# 1_Wearable_Air_Quality_Pendant.net
KiCad netlist of a schematic drawn in Altium Designer
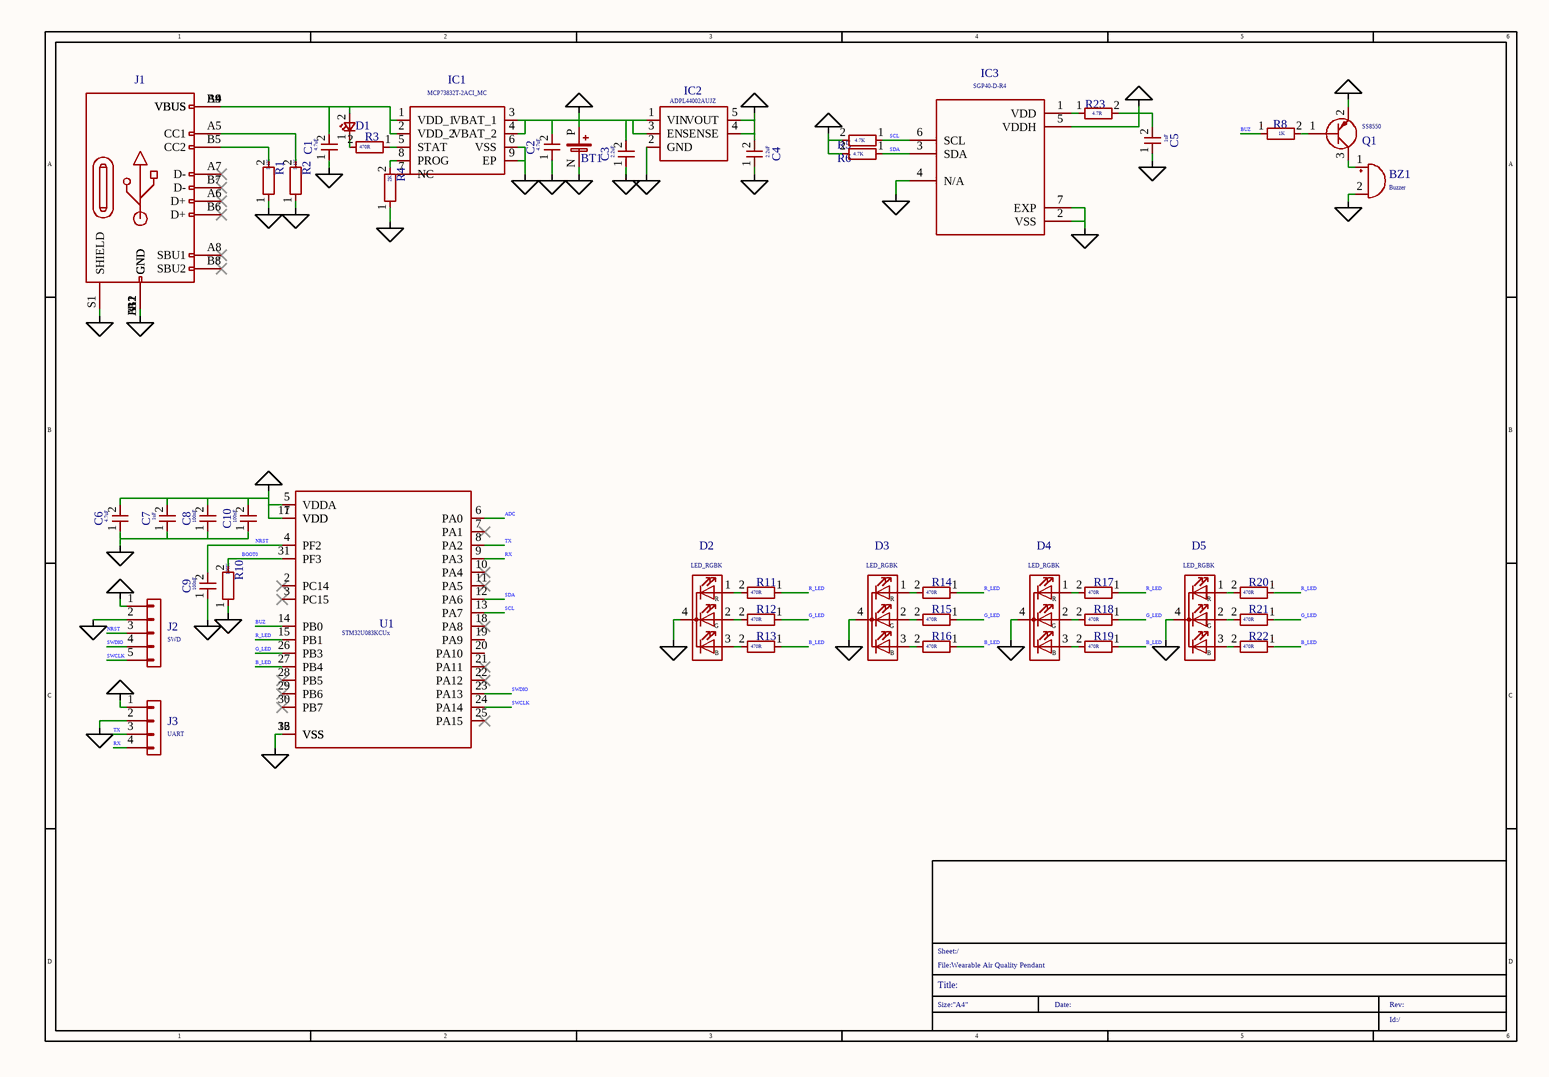
[diagram p0: 1_Wearable Air Quality Pendant.schdoc]

(export (version "E")
  (design (tool "Eeschema 10.0.6"))
  (components
    (comp (ref "BT1")
      (value "Device_Battery_Cell")
      (footprint "1060:BAT_1060")
      (libsource (lib "altium-import") (part "root_0_Device_Battery_Cell_"))
    )
    (comp (ref "BZ1")
      (value "Device_Buzzer")
      (footprint "PKMCS0909E4000_R1:PKMCS0909E4000-R1_MUR")
      (fields (field (name "ALTIUM_VALUE") "Buzzer"))
      (libsource (lib "altium-import") (part "root_0_Device_Buzzer_"))
    )
    (comp (ref "C1")
      (value "Device_C_Small")
      (footprint "Capacitor_SMD:C_0603_1608Metric")
      (fields (field (name "ALTIUM_VALUE") "4.7uF"))
      (libsource (lib "altium-import") (part "root_2_Device_C_Small_"))
    )
    (comp (ref "C2")
      (value "Device_C_Small")
      (footprint "Capacitor_SMD:C_0603_1608Metric")
      (fields (field (name "ALTIUM_VALUE") "4.7uF"))
      (libsource (lib "altium-import") (part "root_2_Device_C_Small_"))
    )
    (comp (ref "C3")
      (value "Device_C_Small")
      (footprint "Capacitor_SMD:C_0603_1608Metric")
      (fields (field (name "ALTIUM_VALUE") "2.2uF"))
      (libsource (lib "altium-import") (part "root_2_Device_C_Small_"))
    )
    (comp (ref "C4")
      (value "Device_C_Small")
      (footprint "Capacitor_SMD:C_0603_1608Metric")
      (fields (field (name "ALTIUM_VALUE") "2.2uF"))
      (libsource (lib "altium-import") (part "root_2_mirrored_Device_C_Small_"))
    )
    (comp (ref "C5")
      (value "Device_C_Small")
      (footprint "Capacitor_SMD:C_0603_1608Metric")
      (fields (field (name "ALTIUM_VALUE") "1uF"))
      (libsource (lib "altium-import") (part "root_2_mirrored_Device_C_Small_"))
    )
    (comp (ref "C6")
      (value "Device_C_Small")
      (footprint "Capacitor_SMD:C_0603_1608Metric")
      (fields (field (name "ALTIUM_VALUE") "4.7uF"))
      (libsource (lib "altium-import") (part "root_2_Device_C_Small_"))
    )
    (comp (ref "C7")
      (value "Device_C_Small")
      (footprint "Capacitor_SMD:C_0603_1608Metric")
      (fields (field (name "ALTIUM_VALUE") "1uF"))
      (libsource (lib "altium-import") (part "root_2_Device_C_Small_"))
    )
    (comp (ref "C8")
      (value "Device_C_Small")
      (footprint "Capacitor_SMD:C_0603_1608Metric")
      (fields (field (name "ALTIUM_VALUE") "100nF"))
      (libsource (lib "altium-import") (part "root_2_Device_C_Small_"))
    )
    (comp (ref "C9")
      (value "Device_C_Small")
      (footprint "Capacitor_SMD:C_0603_1608Metric")
      (fields (field (name "ALTIUM_VALUE") "100nF"))
      (libsource (lib "altium-import") (part "root_2_Device_C_Small_"))
    )
    (comp (ref "C10")
      (value "Device_C_Small")
      (footprint "Capacitor_SMD:C_0603_1608Metric")
      (fields (field (name "ALTIUM_VALUE") "100nF"))
      (libsource (lib "altium-import") (part "root_2_Device_C_Small_"))
    )
    (comp (ref "D1")
      (value "Device_LED_Small")
      (footprint "LED_SMD:LED_0603_1608Metric")
      (libsource (lib "altium-import") (part "root_1_Device_LED_Small_"))
    )
    (comp (ref "D2")
      (value "Device_LED_RGBK")
      (footprint "EAST1616RGBA1:EAST1616RGBA1")
      (fields (field (name "ALTIUM_VALUE") "LED_RGBK"))
      (libsource (lib "altium-import") (part "root_0_Device_LED_RGBK_"))
    )
    (comp (ref "D3")
      (value "Device_LED_RGBK")
      (footprint "EAST1616RGBA1:EAST1616RGBA1")
      (fields (field (name "ALTIUM_VALUE") "LED_RGBK"))
      (libsource (lib "altium-import") (part "root_0_Device_LED_RGBK_"))
    )
    (comp (ref "D4")
      (value "Device_LED_RGBK")
      (footprint "EAST1616RGBA1:EAST1616RGBA1")
      (fields (field (name "ALTIUM_VALUE") "LED_RGBK"))
      (libsource (lib "altium-import") (part "root_0_Device_LED_RGBK_"))
    )
    (comp (ref "D5")
      (value "Device_LED_RGBK")
      (footprint "EAST1616RGBA1:EAST1616RGBA1")
      (fields (field (name "ALTIUM_VALUE") "LED_RGBK"))
      (libsource (lib "altium-import") (part "root_0_Device_LED_RGBK_"))
    )
    (comp (ref "IC1")
      (value "MCP73832T-2ACI_MC_MCP73832T-2ACI_MC")
      (footprint "MCP73832T-2ACI_MC:SON50P300X200X100-9N-D")
      (fields
        (field (name "MOUSER PART NUMBER") "579-MCP73832T-2ACIMC")
        (field (name "MANUFACTURER_PART_NUMBER") "MCP73832T-2ACI/MC")
        (field (name "ALTIUM_VALUE") "MCP73832T-2ACI_MC")
      )
      (libsource (lib "altium-import") (part "root_0_MCP73832T-2ACI_MC_MCP73832T-2ACI_MC_"))
    )
    (comp (ref "IC2")
      (value "ADPL44002AUJZ-3_3-R7_ADPL44002AUJZ-3.3-R7")
      (footprint "ADPL44002AUJZ-3.3-R7:SOT95P280X100-5N")
      (fields
        (field (name "MANUFACTURER_PART_NUMBER") "ADPL44002AUJZ2.5-R7")
        (field (name "ALTIUM_VALUE") "ADPL44002AUJZ")
      )
      (libsource (lib "altium-import") (part "root_0_ADPL44002AUJZ-3_3-R7_ADPL44002AUJZ-3.3-R7_"))
    )
    (comp (ref "IC3")
      (value "SGP40-D-R4_SGP40-D-R4")
      (footprint "SGP40_D_R4:XCDR_SGP40-D-R4")
      (fields (field (name "MANUFACTURER") "Sensirion AG") (field (name "ALTIUM_VALUE") "SGP40-D-R4"))
      (libsource (lib "altium-import") (part "root_0_SGP40-D-R4_SGP40-D-R4_"))
    )
    (comp (ref "J1")
      (value "Connector_USB_C_Receptacle_USB2.0_16P")
      (footprint "Connector_USB:USB_C_Receptacle_Palconn_UTC16-G")
      (libsource (lib "altium-import") (part "root_0_Connector_USB_C_Receptacle_USB2.0_16P_"))
    )
    (comp (ref "J2")
      (value "Connector_Generic_Conn_01x05")
      (footprint "Connector_PinHeader_1.27mm:PinHeader_1x06_P1.27mm_Vertical")
      (fields (field (name "ALTIUM_VALUE") "SWD"))
      (libsource (lib "altium-import") (part "root_0_Connector_Generic_Conn_01x05_"))
    )
    (comp (ref "J3")
      (value "Connector_Generic_Conn_01x04")
      (footprint "Connector_PinHeader_1.27mm:PinHeader_1x04_P1.27mm_Vertical")
      (fields (field (name "ALTIUM_VALUE") "UART"))
      (libsource (lib "altium-import") (part "root_0_Connector_Generic_Conn_01x04_"))
    )
    (comp (ref "Q1")
      (value "Transistor_BJT_SS8550")
      (footprint "Package_TO_SOT_SMD:SOT-23")
      (fields (field (name "ALTIUM_VALUE") "SS8550"))
      (libsource (lib "altium-import") (part "root_2_mirrored_Transistor_BJT_SS8550_"))
    )
    (comp (ref "R1")
      (value "Device_R")
      (footprint "Resistor_SMD:R_0603_1608Metric")
      (fields (field (name "ALTIUM_VALUE") "5.1K"))
      (libsource (lib "altium-import") (part "root_2_Device_R_"))
    )
    (comp (ref "R2")
      (value "Device_R")
      (footprint "Resistor_SMD:R_0603_1608Metric")
      (fields (field (name "ALTIUM_VALUE") "5.1K"))
      (libsource (lib "altium-import") (part "root_2_Device_R_"))
    )
    (comp (ref "R3")
      (value "Device_R")
      (footprint "Resistor_SMD:R_0603_1608Metric")
      (fields (field (name "ALTIUM_VALUE") "470R"))
      (libsource (lib "altium-import") (part "root_3_Device_R_"))
    )
    (comp (ref "R4")
      (value "Device_R")
      (footprint "Resistor_SMD:R_0603_1608Metric")
      (fields (field (name "ALTIUM_VALUE") "2K"))
      (libsource (lib "altium-import") (part "root_2_Device_R_"))
    )
    (comp (ref "R5")
      (value "Device_R")
      (footprint "Resistor_SMD:R_0603_1608Metric")
      (fields (field (name "ALTIUM_VALUE") "4.7K"))
      (libsource (lib "altium-import") (part "root_3_Device_R_"))
    )
    (comp (ref "R6")
      (value "Device_R")
      (footprint "Resistor_SMD:R_0603_1608Metric")
      (fields (field (name "ALTIUM_VALUE") "4.7K"))
      (libsource (lib "altium-import") (part "root_1_mirrored_Device_R_"))
    )
    (comp (ref "R8")
      (value "Device_R")
      (footprint "Resistor_SMD:R_0603_1608Metric")
      (fields (field (name "ALTIUM_VALUE") "1K"))
      (libsource (lib "altium-import") (part "root_3_mirrored_Device_R_"))
    )
    (comp (ref "R10")
      (value "Device_R")
      (footprint "Resistor_SMD:R_0603_1608Metric")
      (fields (field (name "ALTIUM_VALUE") "100K"))
      (libsource (lib "altium-import") (part "root_2_Device_R_"))
    )
    (comp (ref "R11")
      (value "Device_R")
      (footprint "Resistor_SMD:R_0603_1608Metric")
      (fields (field (name "ALTIUM_VALUE") "470R"))
      (libsource (lib "altium-import") (part "root_3_Device_R_"))
    )
    (comp (ref "R12")
      (value "Device_R")
      (footprint "Resistor_SMD:R_0603_1608Metric")
      (fields (field (name "ALTIUM_VALUE") "470R"))
      (libsource (lib "altium-import") (part "root_3_Device_R_"))
    )
    (comp (ref "R13")
      (value "Device_R")
      (footprint "Resistor_SMD:R_0603_1608Metric")
      (fields (field (name "ALTIUM_VALUE") "470R"))
      (libsource (lib "altium-import") (part "root_3_Device_R_"))
    )
    (comp (ref "R14")
      (value "Device_R")
      (footprint "Resistor_SMD:R_0603_1608Metric")
      (fields (field (name "ALTIUM_VALUE") "470R"))
      (libsource (lib "altium-import") (part "root_3_Device_R_"))
    )
    (comp (ref "R15")
      (value "Device_R")
      (footprint "Resistor_SMD:R_0603_1608Metric")
      (fields (field (name "ALTIUM_VALUE") "470R"))
      (libsource (lib "altium-import") (part "root_3_Device_R_"))
    )
    (comp (ref "R16")
      (value "Device_R")
      (footprint "Resistor_SMD:R_0603_1608Metric")
      (fields (field (name "ALTIUM_VALUE") "470R"))
      (libsource (lib "altium-import") (part "root_3_Device_R_"))
    )
    (comp (ref "R17")
      (value "Device_R")
      (footprint "Resistor_SMD:R_0603_1608Metric")
      (fields (field (name "ALTIUM_VALUE") "470R"))
      (libsource (lib "altium-import") (part "root_3_Device_R_"))
    )
    (comp (ref "R18")
      (value "Device_R")
      (footprint "Resistor_SMD:R_0603_1608Metric")
      (fields (field (name "ALTIUM_VALUE") "470R"))
      (libsource (lib "altium-import") (part "root_3_Device_R_"))
    )
    (comp (ref "R19")
      (value "Device_R")
      (footprint "Resistor_SMD:R_0603_1608Metric")
      (fields (field (name "ALTIUM_VALUE") "470R"))
      (libsource (lib "altium-import") (part "root_3_Device_R_"))
    )
    (comp (ref "R20")
      (value "Device_R")
      (footprint "Resistor_SMD:R_0603_1608Metric")
      (fields (field (name "ALTIUM_VALUE") "470R"))
      (libsource (lib "altium-import") (part "root_3_Device_R_"))
    )
    (comp (ref "R21")
      (value "Device_R")
      (footprint "Resistor_SMD:R_0603_1608Metric")
      (fields (field (name "ALTIUM_VALUE") "470R"))
      (libsource (lib "altium-import") (part "root_3_Device_R_"))
    )
    (comp (ref "R22")
      (value "Device_R")
      (footprint "Resistor_SMD:R_0603_1608Metric")
      (fields (field (name "ALTIUM_VALUE") "470R"))
      (libsource (lib "altium-import") (part "root_3_Device_R_"))
    )
    (comp (ref "R23")
      (value "Device_R")
      (footprint "Resistor_SMD:R_0805_2012Metric")
      (fields (field (name "ALTIUM_VALUE") "4.7R"))
      (libsource (lib "altium-import") (part "root_3_mirrored_Device_R_"))
    )
    (comp (ref "U1")
      (value "MCU_ST_STM32U0_STM32U083KCUx")
      (footprint "Package_DFN_QFN:QFN-32-1EP_5x5mm_P0.5mm_EP3.45x3.45mm")
      (fields (field (name "ALTIUM_VALUE") "STM32U083KCUx"))
      (libsource (lib "altium-import") (part "root_0_MCU_ST_STM32U0_STM32U083KCUx_"))
    )
  )
  (nets
    (net (code "1") (name "/ADC") (class "Default")
      (node (ref "U1") (pin "6") (pinfunction "PA0_6") (pintype "passive"))
    )
    (net (code "2") (name "/BOOT0") (class "Default")
      (node (ref "R10") (pin "2") (pintype "passive"))
      (node (ref "U1") (pin "31") (pinfunction "PF3_31") (pintype "passive"))
    )
    (net (code "3") (name "/BUZ") (class "Default")
      (node (ref "R8") (pin "1") (pintype "passive"))
      (node (ref "U1") (pin "14") (pinfunction "PB0_14") (pintype "passive"))
    )
    (net (code "4") (name "/B_LED") (class "Default")
      (node (ref "R13") (pin "1") (pintype "passive"))
      (node (ref "R16") (pin "1") (pintype "passive"))
      (node (ref "R19") (pin "1") (pintype "passive"))
      (node (ref "R22") (pin "1") (pintype "passive"))
      (node (ref "U1") (pin "27") (pinfunction "PB4_27") (pintype "passive"))
    )
    (net (code "5") (name "/G_LED") (class "Default")
      (node (ref "R12") (pin "1") (pintype "passive"))
      (node (ref "R15") (pin "1") (pintype "passive"))
      (node (ref "R18") (pin "1") (pintype "passive"))
      (node (ref "R21") (pin "1") (pintype "passive"))
      (node (ref "U1") (pin "26") (pinfunction "PB3_26") (pintype "passive"))
    )
    (net (code "6") (name "/NRST") (class "Default")
      (node (ref "C9") (pin "2") (pintype "passive"))
      (node (ref "J2") (pin "3") (pinfunction "Pin_3_3") (pintype "passive"))
      (node (ref "U1") (pin "4") (pinfunction "PF2_4") (pintype "passive"))
    )
    (net (code "7") (name "/RX") (class "Default")
      (node (ref "J3") (pin "4") (pinfunction "Pin_4_4") (pintype "passive"))
      (node (ref "U1") (pin "9") (pinfunction "PA3_9") (pintype "passive"))
    )
    (net (code "8") (name "/R_LED") (class "Default")
      (node (ref "R11") (pin "1") (pintype "passive"))
      (node (ref "R14") (pin "1") (pintype "passive"))
      (node (ref "R17") (pin "1") (pintype "passive"))
      (node (ref "R20") (pin "1") (pintype "passive"))
      (node (ref "U1") (pin "15") (pinfunction "PB1_15") (pintype "passive"))
    )
    (net (code "9") (name "/SCL") (class "Default")
      (node (ref "IC3") (pin "6") (pinfunction "SCL_6") (pintype "passive"))
      (node (ref "R5") (pin "1") (pintype "passive"))
      (node (ref "U1") (pin "13") (pinfunction "PA7_13") (pintype "passive"))
    )
    (net (code "10") (name "/SDA") (class "Default")
      (node (ref "IC3") (pin "3") (pinfunction "SDA_3") (pintype "passive"))
      (node (ref "R6") (pin "1") (pintype "passive"))
      (node (ref "U1") (pin "12") (pinfunction "PA6_12") (pintype "passive"))
    )
    (net (code "11") (name "/SWCLK") (class "Default")
      (node (ref "J2") (pin "5") (pinfunction "Pin_5_5") (pintype "passive"))
      (node (ref "U1") (pin "24") (pinfunction "PA14_24") (pintype "passive"))
    )
    (net (code "12") (name "/SWDIO") (class "Default")
      (node (ref "J2") (pin "4") (pinfunction "Pin_4_4") (pintype "passive"))
      (node (ref "U1") (pin "23") (pinfunction "PA13_23") (pintype "passive"))
    )
    (net (code "13") (name "/TX") (class "Default")
      (node (ref "J3") (pin "3") (pinfunction "Pin_3_3") (pintype "passive"))
      (node (ref "U1") (pin "8") (pinfunction "PA2_8") (pintype "passive"))
    )
    (net (code "14") (name "Net-(BZ1-+)") (class "Default")
      (node (ref "BZ1") (pin "1") (pinfunction "+_1") (pintype "passive"))
      (node (ref "Q1") (pin "3") (pinfunction "C_3") (pintype "passive"))
    )
    (net (code "15") (name "Net-(D1-A)") (class "Default")
      (node (ref "C1") (pin "2") (pintype "passive"))
      (node (ref "D1") (pin "2") (pinfunction "A_2") (pintype "passive"))
      (node (ref "IC1") (pin "1") (pinfunction "VDD_1_1") (pintype "passive"))
      (node (ref "IC1") (pin "2") (pinfunction "VDD_2_2") (pintype "passive"))
      (node (ref "J1") (pin "A4") (pinfunction "VBUS_A4") (pintype "passive"))
      (node (ref "J1") (pin "A9") (pinfunction "VBUS_A9") (pintype "passive"))
      (node (ref "J1") (pin "B4") (pinfunction "VBUS_B4") (pintype "passive"))
      (node (ref "J1") (pin "B9") (pinfunction "VBUS_B9") (pintype "passive"))
    )
    (net (code "16") (name "Net-(D1-K)") (class "Default")
      (node (ref "D1") (pin "1") (pinfunction "K_1") (pintype "passive"))
      (node (ref "R3") (pin "2") (pintype "passive"))
    )
    (net (code "17") (name "Net-(D2-BA)") (class "Default")
      (node (ref "D2") (pin "3") (pinfunction "BA_3") (pintype "passive"))
      (node (ref "R13") (pin "2") (pintype "passive"))
    )
    (net (code "18") (name "Net-(D2-GA)") (class "Default")
      (node (ref "D2") (pin "2") (pinfunction "GA_2") (pintype "passive"))
      (node (ref "R12") (pin "2") (pintype "passive"))
    )
    (net (code "19") (name "Net-(D2-RA)") (class "Default")
      (node (ref "D2") (pin "1") (pinfunction "RA_1") (pintype "passive"))
      (node (ref "R11") (pin "2") (pintype "passive"))
    )
    (net (code "20") (name "Net-(D3-BA)") (class "Default")
      (node (ref "D3") (pin "3") (pinfunction "BA_3") (pintype "passive"))
      (node (ref "R16") (pin "2") (pintype "passive"))
    )
    (net (code "21") (name "Net-(D3-GA)") (class "Default")
      (node (ref "D3") (pin "2") (pinfunction "GA_2") (pintype "passive"))
      (node (ref "R15") (pin "2") (pintype "passive"))
    )
    (net (code "22") (name "Net-(D3-RA)") (class "Default")
      (node (ref "D3") (pin "1") (pinfunction "RA_1") (pintype "passive"))
      (node (ref "R14") (pin "2") (pintype "passive"))
    )
    (net (code "23") (name "Net-(D4-BA)") (class "Default")
      (node (ref "D4") (pin "3") (pinfunction "BA_3") (pintype "passive"))
      (node (ref "R19") (pin "2") (pintype "passive"))
    )
    (net (code "24") (name "Net-(D4-GA)") (class "Default")
      (node (ref "D4") (pin "2") (pinfunction "GA_2") (pintype "passive"))
      (node (ref "R18") (pin "2") (pintype "passive"))
    )
    (net (code "25") (name "Net-(D4-RA)") (class "Default")
      (node (ref "D4") (pin "1") (pinfunction "RA_1") (pintype "passive"))
      (node (ref "R17") (pin "2") (pintype "passive"))
    )
    (net (code "26") (name "Net-(D5-BA)") (class "Default")
      (node (ref "D5") (pin "3") (pinfunction "BA_3") (pintype "passive"))
      (node (ref "R22") (pin "2") (pintype "passive"))
    )
    (net (code "27") (name "Net-(D5-GA)") (class "Default")
      (node (ref "D5") (pin "2") (pinfunction "GA_2") (pintype "passive"))
      (node (ref "R21") (pin "2") (pintype "passive"))
    )
    (net (code "28") (name "Net-(D5-RA)") (class "Default")
      (node (ref "D5") (pin "1") (pinfunction "RA_1") (pintype "passive"))
      (node (ref "R20") (pin "2") (pintype "passive"))
    )
    (net (code "29") (name "Net-(IC1-PROG)") (class "Default")
      (node (ref "IC1") (pin "8") (pinfunction "PROG_8") (pintype "passive"))
      (node (ref "R4") (pin "2") (pintype "passive"))
    )
    (net (code "30") (name "Net-(IC1-STAT)") (class "Default")
      (node (ref "IC1") (pin "5") (pinfunction "STAT_5") (pintype "passive"))
      (node (ref "R3") (pin "1") (pintype "passive"))
    )
    (net (code "31") (name "Net-(IC3-VDD)") (class "Default")
      (node (ref "IC3") (pin "1") (pinfunction "VDD_1") (pintype "passive"))
      (node (ref "R23") (pin "1") (pintype "passive"))
    )
    (net (code "32") (name "Net-(J1-CC1)") (class "Default")
      (node (ref "J1") (pin "A5") (pinfunction "CC1_A5") (pintype "passive"))
      (node (ref "R2") (pin "2") (pintype "passive"))
    )
    (net (code "33") (name "Net-(J1-CC2)") (class "Default")
      (node (ref "J1") (pin "B5") (pinfunction "CC2_B5") (pintype "passive"))
      (node (ref "R1") (pin "2") (pintype "passive"))
    )
    (net (code "34") (name "Net-(Q1-B)") (class "Default")
      (node (ref "Q1") (pin "1") (pinfunction "B_1") (pintype "passive"))
      (node (ref "R8") (pin "2") (pintype "passive"))
    )
    (net (code "35") (name "POWER_+3.3V") (class "Default")
      (node (ref "C10") (pin "2") (pintype "passive"))
      (node (ref "C4") (pin "2") (pintype "passive"))
      (node (ref "C5") (pin "2") (pintype "passive"))
      (node (ref "C6") (pin "2") (pintype "passive"))
      (node (ref "C7") (pin "2") (pintype "passive"))
      (node (ref "C8") (pin "2") (pintype "passive"))
      (node (ref "IC2") (pin "4") (pinfunction "SENSE_4") (pintype "passive"))
      (node (ref "IC2") (pin "5") (pinfunction "VOUT_5") (pintype "passive"))
      (node (ref "IC3") (pin "5") (pinfunction "VDDH_5") (pintype "passive"))
      (node (ref "J2") (pin "1") (pinfunction "Pin_1_1") (pintype "passive"))
      (node (ref "J3") (pin "1") (pinfunction "Pin_1_1") (pintype "passive"))
      (node (ref "Q1") (pin "2") (pinfunction "E_2") (pintype "passive"))
      (node (ref "R23") (pin "2") (pintype "passive"))
      (node (ref "R5") (pin "2") (pintype "passive"))
      (node (ref "R6") (pin "2") (pintype "passive"))
      (node (ref "U1") (pin "1") (pinfunction "VDD_1") (pintype "passive"))
      (node (ref "U1") (pin "17") (pinfunction "VDD_17") (pintype "passive"))
      (node (ref "U1") (pin "5") (pinfunction "VDDA_5") (pintype "passive"))
    )
    (net (code "36") (name "POWER_+BATT") (class "Default")
      (node (ref "BT1") (pin "P") (pinfunction "+_P") (pintype "passive"))
      (node (ref "C2") (pin "2") (pintype "passive"))
      (node (ref "C3") (pin "2") (pintype "passive"))
      (node (ref "IC1") (pin "3") (pinfunction "VBAT_1_3") (pintype "passive"))
      (node (ref "IC1") (pin "4") (pinfunction "VBAT_2_4") (pintype "passive"))
      (node (ref "IC2") (pin "1") (pinfunction "VIN_1") (pintype "passive"))
      (node (ref "IC2") (pin "3") (pinfunction "EN_3") (pintype "passive"))
    )
    (net (code "37") (name "POWER_GND") (class "Default")
      (node (ref "BT1") (pin "N") (pinfunction "-_N") (pintype "passive"))
      (node (ref "BZ1") (pin "2") (pinfunction "-_2") (pintype "passive"))
      (node (ref "C1") (pin "1") (pintype "passive"))
      (node (ref "C10") (pin "1") (pintype "passive"))
      (node (ref "C2") (pin "1") (pintype "passive"))
      (node (ref "C3") (pin "1") (pintype "passive"))
      (node (ref "C4") (pin "1") (pintype "passive"))
      (node (ref "C5") (pin "1") (pintype "passive"))
      (node (ref "C6") (pin "1") (pintype "passive"))
      (node (ref "C7") (pin "1") (pintype "passive"))
      (node (ref "C8") (pin "1") (pintype "passive"))
      (node (ref "C9") (pin "1") (pintype "passive"))
      (node (ref "D2") (pin "4") (pinfunction "K_4") (pintype "passive"))
      (node (ref "D3") (pin "4") (pinfunction "K_4") (pintype "passive"))
      (node (ref "D4") (pin "4") (pinfunction "K_4") (pintype "passive"))
      (node (ref "D5") (pin "4") (pinfunction "K_4") (pintype "passive"))
      (node (ref "IC1") (pin "6") (pinfunction "VSS_6") (pintype "passive"))
      (node (ref "IC1") (pin "9") (pinfunction "EP_9") (pintype "passive"))
      (node (ref "IC2") (pin "2") (pinfunction "GND_2") (pintype "passive"))
      (node (ref "IC3") (pin "2") (pinfunction "VSS_2") (pintype "passive"))
      (node (ref "IC3") (pin "4") (pinfunction "N/A_4") (pintype "passive"))
      (node (ref "IC3") (pin "7") (pinfunction "EXP_7") (pintype "passive"))
      (node (ref "J1") (pin "A1") (pinfunction "GND_A1") (pintype "passive"))
      (node (ref "J1") (pin "A12") (pinfunction "GND_A12") (pintype "passive"))
      (node (ref "J1") (pin "B1") (pinfunction "GND_B1") (pintype "passive"))
      (node (ref "J1") (pin "B12") (pinfunction "GND_B12") (pintype "passive"))
      (node (ref "J1") (pin "S1") (pinfunction "SHIELD_S1") (pintype "passive"))
      (node (ref "J2") (pin "2") (pinfunction "Pin_2_2") (pintype "passive"))
      (node (ref "J3") (pin "2") (pinfunction "Pin_2_2") (pintype "passive"))
      (node (ref "R1") (pin "1") (pintype "passive"))
      (node (ref "R10") (pin "1") (pintype "passive"))
      (node (ref "R2") (pin "1") (pintype "passive"))
      (node (ref "R4") (pin "1") (pintype "passive"))
      (node (ref "U1") (pin "16") (pinfunction "VSS_16") (pintype "passive"))
      (node (ref "U1") (pin "32") (pinfunction "VSS_32") (pintype "passive"))
      (node (ref "U1") (pin "33") (pinfunction "VSS_33") (pintype "passive"))
    )
    (net (code "38") (name "unconnected-(IC1-NC-Pad7)") (class "Default")
      (node (ref "IC1") (pin "7") (pinfunction "NC_7") (pintype "passive"))
    )
    (net (code "39") (name "unconnected-(J1-D+-PadA6)") (class "Default")
      (node (ref "J1") (pin "A6") (pinfunction "D+_A6") (pintype "passive+no_connect"))
    )
    (net (code "40") (name "unconnected-(J1-D+-PadB6)") (class "Default")
      (node (ref "J1") (pin "B6") (pinfunction "D+_B6") (pintype "passive+no_connect"))
    )
    (net (code "41") (name "unconnected-(J1-D--PadA7)") (class "Default")
      (node (ref "J1") (pin "A7") (pinfunction "D-_A7") (pintype "passive+no_connect"))
    )
    (net (code "42") (name "unconnected-(J1-D--PadB7)") (class "Default")
      (node (ref "J1") (pin "B7") (pinfunction "D-_B7") (pintype "passive+no_connect"))
    )
    (net (code "43") (name "unconnected-(J1-SBU1-PadA8)") (class "Default")
      (node (ref "J1") (pin "A8") (pinfunction "SBU1_A8") (pintype "passive+no_connect"))
    )
    (net (code "44") (name "unconnected-(J1-SBU2-PadB8)") (class "Default")
      (node (ref "J1") (pin "B8") (pinfunction "SBU2_B8") (pintype "passive+no_connect"))
    )
    (net (code "45") (name "unconnected-(U1-PA1-Pad7)") (class "Default")
      (node (ref "U1") (pin "7") (pinfunction "PA1_7") (pintype "passive+no_connect"))
    )
    (net (code "46") (name "unconnected-(U1-PA4-Pad10)") (class "Default")
      (node (ref "U1") (pin "10") (pinfunction "PA4_10") (pintype "passive+no_connect"))
    )
    (net (code "47") (name "unconnected-(U1-PA5-Pad11)") (class "Default")
      (node (ref "U1") (pin "11") (pinfunction "PA5_11") (pintype "passive+no_connect"))
    )
    (net (code "48") (name "unconnected-(U1-PA8-Pad18)") (class "Default")
      (node (ref "U1") (pin "18") (pinfunction "PA8_18") (pintype "passive+no_connect"))
    )
    (net (code "49") (name "unconnected-(U1-PA9-Pad19)") (class "Default")
      (node (ref "U1") (pin "19") (pinfunction "PA9_19") (pintype "passive"))
    )
    (net (code "50") (name "unconnected-(U1-PA10-Pad20)") (class "Default")
      (node (ref "U1") (pin "20") (pinfunction "PA10_20") (pintype "passive"))
    )
    (net (code "51") (name "unconnected-(U1-PA11-Pad21)") (class "Default")
      (node (ref "U1") (pin "21") (pinfunction "PA11_21") (pintype "passive+no_connect"))
    )
    (net (code "52") (name "unconnected-(U1-PA12-Pad22)") (class "Default")
      (node (ref "U1") (pin "22") (pinfunction "PA12_22") (pintype "passive+no_connect"))
    )
    (net (code "53") (name "unconnected-(U1-PA15-Pad25)") (class "Default")
      (node (ref "U1") (pin "25") (pinfunction "PA15_25") (pintype "passive+no_connect"))
    )
    (net (code "54") (name "unconnected-(U1-PB5-Pad28)") (class "Default")
      (node (ref "U1") (pin "28") (pinfunction "PB5_28") (pintype "passive+no_connect"))
    )
    (net (code "55") (name "unconnected-(U1-PB6-Pad29)") (class "Default")
      (node (ref "U1") (pin "29") (pinfunction "PB6_29") (pintype "passive+no_connect"))
    )
    (net (code "56") (name "unconnected-(U1-PB7-Pad30)") (class "Default")
      (node (ref "U1") (pin "30") (pinfunction "PB7_30") (pintype "passive+no_connect"))
    )
    (net (code "57") (name "unconnected-(U1-PC14-Pad2)") (class "Default")
      (node (ref "U1") (pin "2") (pinfunction "PC14_2") (pintype "passive+no_connect"))
    )
    (net (code "58") (name "unconnected-(U1-PC15-Pad3)") (class "Default")
      (node (ref "U1") (pin "3") (pinfunction "PC15_3") (pintype "passive+no_connect"))
    )
  )
)
